# v1.net
KiCad netlist of a schematic drawn in EAGLE
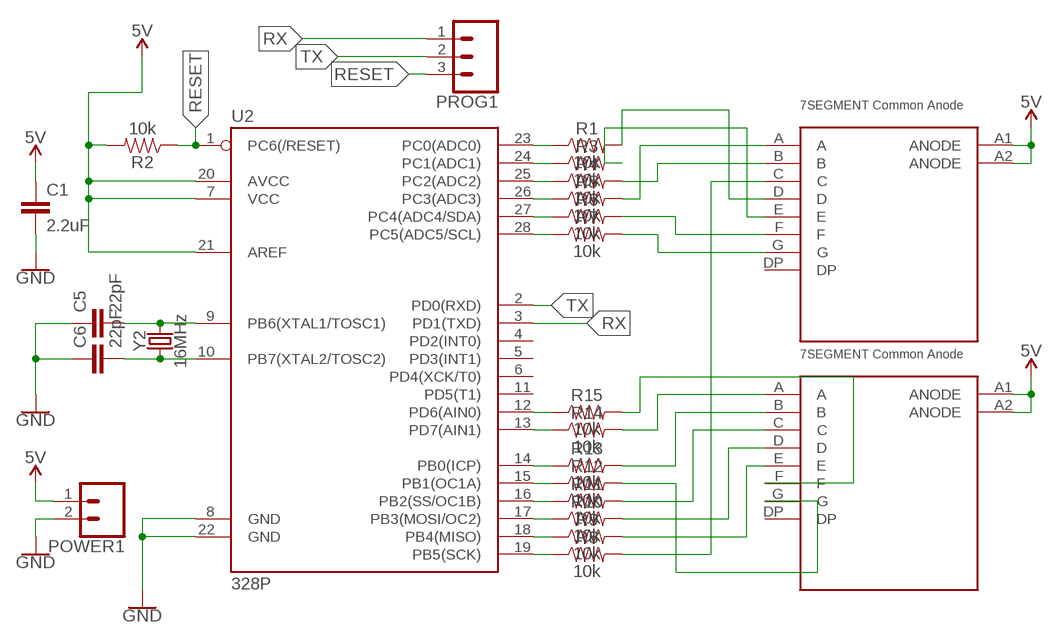
[diagram p0: schematic, sheet 1]

(export (version "E")
  (design (tool "Eeschema 10.0.6"))
  (components
    (comp (ref "C1")
      (value "2.2uF")
      (footprint "eagle-import:1206")
      (libsource (lib "eagle-import") (part "2.2UF-1206-50V-10%"))
    )
    (comp (ref "C5")
      (value "22pF")
      (footprint "eagle-import:CAP-PTH-2.54")
      (libsource (lib "eagle-import") (part "22PF-PTH-2.54MM-200V-5%"))
    )
    (comp (ref "C6")
      (value "22pF")
      (footprint "eagle-import:CAP-PTH-2.54")
      (libsource (lib "eagle-import") (part "22PF-PTH-2.54MM-200V-5%"))
    )
    (comp (ref "POWER1")
      (value "CONN_02")
      (footprint "eagle-import:1X02")
      (libsource (lib "eagle-import") (part "CONN_02"))
    )
    (comp (ref "PROG1")
      (value "CONN_03")
      (footprint "eagle-import:1X03")
      (libsource (lib "eagle-import") (part "CONN_03"))
    )
    (comp (ref "R1")
      (value "10k")
      (footprint "eagle-import:0805")
      (libsource (lib "eagle-import") (part "0.22OHM-0805-1/4W-1%"))
    )
    (comp (ref "R2")
      (value "10k")
      (footprint "eagle-import:AXIAL-0.3")
      (libsource (lib "eagle-import") (part "1KOHM-HORIZ-1/4W-1%"))
    )
    (comp (ref "R3")
      (value "10k")
      (footprint "eagle-import:0805")
      (libsource (lib "eagle-import") (part "0.22OHM-0805-1/4W-1%"))
    )
    (comp (ref "R4")
      (value "10k")
      (footprint "eagle-import:0805")
      (libsource (lib "eagle-import") (part "0.22OHM-0805-1/4W-1%"))
    )
    (comp (ref "R5")
      (value "10k")
      (footprint "eagle-import:0805")
      (libsource (lib "eagle-import") (part "0.22OHM-0805-1/4W-1%"))
    )
    (comp (ref "R6")
      (value "10k")
      (footprint "eagle-import:0805")
      (libsource (lib "eagle-import") (part "0.22OHM-0805-1/4W-1%"))
    )
    (comp (ref "R7")
      (value "10k")
      (footprint "eagle-import:0805")
      (libsource (lib "eagle-import") (part "0.22OHM-0805-1/4W-1%"))
    )
    (comp (ref "R8")
      (value "10k")
      (footprint "eagle-import:0805")
      (libsource (lib "eagle-import") (part "0.22OHM-0805-1/4W-1%"))
    )
    (comp (ref "R9")
      (value "10k")
      (footprint "eagle-import:0805")
      (libsource (lib "eagle-import") (part "0.22OHM-0805-1/4W-1%"))
    )
    (comp (ref "R10")
      (value "10k")
      (footprint "eagle-import:0805")
      (libsource (lib "eagle-import") (part "0.22OHM-0805-1/4W-1%"))
    )
    (comp (ref "R11")
      (value "10k")
      (footprint "eagle-import:0805")
      (libsource (lib "eagle-import") (part "0.22OHM-0805-1/4W-1%"))
    )
    (comp (ref "R12")
      (value "10k")
      (footprint "eagle-import:0805")
      (libsource (lib "eagle-import") (part "0.22OHM-0805-1/4W-1%"))
    )
    (comp (ref "R13")
      (value "10k")
      (footprint "eagle-import:0805")
      (libsource (lib "eagle-import") (part "0.22OHM-0805-1/4W-1%"))
    )
    (comp (ref "R14")
      (value "10k")
      (footprint "eagle-import:0805")
      (libsource (lib "eagle-import") (part "0.22OHM-0805-1/4W-1%"))
    )
    (comp (ref "R15")
      (value "10k")
      (footprint "eagle-import:0805")
      (libsource (lib "eagle-import") (part "0.22OHM-0805-1/4W-1%"))
    )
    (comp (ref "U$1")
      (value "7SEGMENTCA")
      (footprint "eagle-import:7SEGMENTCA")
      (libsource (lib "eagle-import") (part "7SEGMENTCA"))
    )
    (comp (ref "U$2")
      (value "7SEGMENTCA")
      (footprint "eagle-import:7SEGMENTCA")
      (libsource (lib "eagle-import") (part "7SEGMENTCA"))
    )
    (comp (ref "U2")
      (value "328P")
      (footprint "eagle-import:DIP28")
      (libsource (lib "eagle-import") (part "ATMEGA328P_PDIP"))
    )
    (comp (ref "Y2")
      (value "16MHz")
      (footprint "eagle-import:HC49US")
      (libsource (lib "eagle-import") (part "CRYSTAL-16MHZPTH-HC49US"))
    )
  )
  (nets
    (net (code "1") (name "5V") (class "Default")
      (node (ref "C1") (pin "1") (pinfunction "1_1") (pintype "passive"))
      (node (ref "POWER1") (pin "1") (pinfunction "1_1") (pintype "passive"))
      (node (ref "R2") (pin "P$2") (pinfunction "2_P$2") (pintype "passive"))
      (node (ref "U$1") (pin "A1") (pinfunction "ANODE_A1") (pintype "bidirectional"))
      (node (ref "U$1") (pin "A2") (pinfunction "ANODE_A2") (pintype "bidirectional"))
      (node (ref "U$2") (pin "A1") (pinfunction "ANODE_A1") (pintype "bidirectional"))
      (node (ref "U$2") (pin "A2") (pinfunction "ANODE_A2") (pintype "bidirectional"))
      (node (ref "U2") (pin "20") (pinfunction "AVCC_20") (pintype "bidirectional"))
      (node (ref "U2") (pin "21") (pinfunction "AREF_21") (pintype "bidirectional"))
      (node (ref "U2") (pin "7") (pinfunction "VCC_7") (pintype "bidirectional"))
    )
    (net (code "2") (name "GND") (class "Default")
      (node (ref "C1") (pin "2") (pinfunction "2_2") (pintype "passive"))
      (node (ref "C5") (pin "1") (pinfunction "1_1") (pintype "passive"))
      (node (ref "C6") (pin "1") (pinfunction "1_1") (pintype "passive"))
      (node (ref "POWER1") (pin "2") (pinfunction "2_2") (pintype "passive"))
      (node (ref "U2") (pin "22") (pinfunction "GND_22") (pintype "bidirectional"))
      (node (ref "U2") (pin "8") (pinfunction "GND_8") (pintype "bidirectional"))
    )
    (net (code "3") (name "Net-(R1-Pad2)") (class "Default")
      (node (ref "R1") (pin "2") (pinfunction "2_2") (pintype "passive"))
      (node (ref "U$1") (pin "D") (pinfunction "D_D") (pintype "bidirectional"))
    )
    (net (code "4") (name "Net-(R3-Pad2)") (class "Default")
      (node (ref "R3") (pin "2") (pinfunction "2_2") (pintype "passive"))
      (node (ref "U$1") (pin "E") (pinfunction "E_E") (pintype "bidirectional"))
    )
    (net (code "5") (name "Net-(R4-Pad2)") (class "Default")
      (node (ref "R4") (pin "2") (pinfunction "2_2") (pintype "passive"))
      (node (ref "U$1") (pin "B") (pinfunction "B_B") (pintype "bidirectional"))
    )
    (net (code "6") (name "Net-(R5-Pad2)") (class "Default")
      (node (ref "R5") (pin "2") (pinfunction "2_2") (pintype "passive"))
      (node (ref "U$1") (pin "A") (pinfunction "A_A") (pintype "bidirectional"))
    )
    (net (code "7") (name "Net-(R6-Pad2)") (class "Default")
      (node (ref "R6") (pin "2") (pinfunction "2_2") (pintype "passive"))
      (node (ref "U$1") (pin "F") (pinfunction "F_F") (pintype "bidirectional"))
    )
    (net (code "8") (name "Net-(R7-Pad2)") (class "Default")
      (node (ref "R7") (pin "2") (pinfunction "2_2") (pintype "passive"))
      (node (ref "U$1") (pin "G") (pinfunction "G_G") (pintype "bidirectional"))
    )
    (net (code "9") (name "Net-(R8-Pad2)") (class "Default")
      (node (ref "R8") (pin "2") (pinfunction "2_2") (pintype "passive"))
      (node (ref "U$1") (pin "C") (pinfunction "C_C") (pintype "bidirectional"))
    )
    (net (code "10") (name "Net-(R9-Pad2)") (class "Default")
      (node (ref "R9") (pin "2") (pinfunction "2_2") (pintype "passive"))
      (node (ref "U$2") (pin "E") (pinfunction "E_E") (pintype "bidirectional"))
    )
    (net (code "11") (name "Net-(R10-Pad2)") (class "Default")
      (node (ref "R10") (pin "2") (pinfunction "2_2") (pintype "passive"))
      (node (ref "U$2") (pin "D") (pinfunction "D_D") (pintype "bidirectional"))
    )
    (net (code "12") (name "Net-(R11-Pad2)") (class "Default")
      (node (ref "R11") (pin "2") (pinfunction "2_2") (pintype "passive"))
      (node (ref "U$2") (pin "C") (pinfunction "C_C") (pintype "bidirectional"))
    )
    (net (code "13") (name "Net-(R12-Pad2)") (class "Default")
      (node (ref "R12") (pin "2") (pinfunction "2_2") (pintype "passive"))
      (node (ref "U$2") (pin "G") (pinfunction "G_G") (pintype "bidirectional"))
    )
    (net (code "14") (name "Net-(R13-Pad2)") (class "Default")
      (node (ref "R13") (pin "2") (pinfunction "2_2") (pintype "passive"))
      (node (ref "U$2") (pin "B") (pinfunction "B_B") (pintype "bidirectional"))
    )
    (net (code "15") (name "Net-(R14-Pad2)") (class "Default")
      (node (ref "R14") (pin "2") (pinfunction "2_2") (pintype "passive"))
      (node (ref "U$2") (pin "A") (pinfunction "A_A") (pintype "bidirectional"))
    )
    (net (code "16") (name "Net-(R15-Pad2)") (class "Default")
      (node (ref "R15") (pin "2") (pinfunction "2_2") (pintype "passive"))
      (node (ref "U$2") (pin "F") (pinfunction "F_F") (pintype "bidirectional"))
    )
    (net (code "17") (name "Net-(U2-PB0(ICP))") (class "Default")
      (node (ref "R13") (pin "1") (pinfunction "1_1") (pintype "passive"))
      (node (ref "U2") (pin "14") (pinfunction "PB0(ICP)_14") (pintype "bidirectional"))
    )
    (net (code "18") (name "Net-(U2-PB1(OC1A))") (class "Default")
      (node (ref "R12") (pin "1") (pinfunction "1_1") (pintype "passive"))
      (node (ref "U2") (pin "15") (pinfunction "PB1(OC1A)_15") (pintype "bidirectional"))
    )
    (net (code "19") (name "Net-(U2-PB2(SS{slash}OC1B))") (class "Default")
      (node (ref "R11") (pin "1") (pinfunction "1_1") (pintype "passive"))
      (node (ref "U2") (pin "16") (pinfunction "PB2(SS/OC1B)_16") (pintype "bidirectional"))
    )
    (net (code "20") (name "Net-(U2-PB3(MOSI{slash}OC2))") (class "Default")
      (node (ref "R10") (pin "1") (pinfunction "1_1") (pintype "passive"))
      (node (ref "U2") (pin "17") (pinfunction "PB3(MOSI/OC2)_17") (pintype "bidirectional"))
    )
    (net (code "21") (name "Net-(U2-PB4(MISO))") (class "Default")
      (node (ref "R9") (pin "1") (pinfunction "1_1") (pintype "passive"))
      (node (ref "U2") (pin "18") (pinfunction "PB4(MISO)_18") (pintype "bidirectional"))
    )
    (net (code "22") (name "Net-(U2-PB5(SCK))") (class "Default")
      (node (ref "R8") (pin "1") (pinfunction "1_1") (pintype "passive"))
      (node (ref "U2") (pin "19") (pinfunction "PB5(SCK)_19") (pintype "bidirectional"))
    )
    (net (code "23") (name "Net-(U2-PB6(XTAL1{slash}TOSC1))") (class "Default")
      (node (ref "C5") (pin "2") (pinfunction "2_2") (pintype "passive"))
      (node (ref "U2") (pin "9") (pinfunction "PB6(XTAL1/TOSC1)_9") (pintype "bidirectional"))
      (node (ref "Y2") (pin "2") (pinfunction "2_2") (pintype "passive"))
    )
    (net (code "24") (name "Net-(U2-PB7(XTAL2{slash}TOSC2))") (class "Default")
      (node (ref "C6") (pin "2") (pinfunction "2_2") (pintype "passive"))
      (node (ref "U2") (pin "10") (pinfunction "PB7(XTAL2/TOSC2)_10") (pintype "bidirectional"))
      (node (ref "Y2") (pin "1") (pinfunction "1_1") (pintype "passive"))
    )
    (net (code "25") (name "Net-(U2-PC0(ADC0))") (class "Default")
      (node (ref "R1") (pin "1") (pinfunction "1_1") (pintype "passive"))
      (node (ref "U2") (pin "23") (pinfunction "PC0(ADC0)_23") (pintype "bidirectional"))
    )
    (net (code "26") (name "Net-(U2-PC1(ADC1))") (class "Default")
      (node (ref "R3") (pin "1") (pinfunction "1_1") (pintype "passive"))
      (node (ref "U2") (pin "24") (pinfunction "PC1(ADC1)_24") (pintype "bidirectional"))
    )
    (net (code "27") (name "Net-(U2-PC2(ADC2))") (class "Default")
      (node (ref "R4") (pin "1") (pinfunction "1_1") (pintype "passive"))
      (node (ref "U2") (pin "25") (pinfunction "PC2(ADC2)_25") (pintype "bidirectional"))
    )
    (net (code "28") (name "Net-(U2-PC3(ADC3))") (class "Default")
      (node (ref "R5") (pin "1") (pinfunction "1_1") (pintype "passive"))
      (node (ref "U2") (pin "26") (pinfunction "PC3(ADC3)_26") (pintype "bidirectional"))
    )
    (net (code "29") (name "Net-(U2-PC4(ADC4{slash}SDA))") (class "Default")
      (node (ref "R6") (pin "1") (pinfunction "1_1") (pintype "passive"))
      (node (ref "U2") (pin "27") (pinfunction "PC4(ADC4/SDA)_27") (pintype "bidirectional"))
    )
    (net (code "30") (name "Net-(U2-PC5(ADC5{slash}SCL))") (class "Default")
      (node (ref "R7") (pin "1") (pinfunction "1_1") (pintype "passive"))
      (node (ref "U2") (pin "28") (pinfunction "PC5(ADC5/SCL)_28") (pintype "bidirectional"))
    )
    (net (code "31") (name "Net-(U2-PD6(AIN0))") (class "Default")
      (node (ref "R15") (pin "1") (pinfunction "1_1") (pintype "passive"))
      (node (ref "U2") (pin "12") (pinfunction "PD6(AIN0)_12") (pintype "bidirectional"))
    )
    (net (code "32") (name "Net-(U2-PD7(AIN1))") (class "Default")
      (node (ref "R14") (pin "1") (pinfunction "1_1") (pintype "passive"))
      (node (ref "U2") (pin "13") (pinfunction "PD7(AIN1)_13") (pintype "bidirectional"))
    )
    (net (code "33") (name "RESET") (class "Default")
      (node (ref "PROG1") (pin "3") (pinfunction "3_3") (pintype "passive"))
      (node (ref "R2") (pin "P$1") (pinfunction "1_P$1") (pintype "passive"))
      (node (ref "U2") (pin "1") (pinfunction "PC6(/RESET)_1") (pintype "bidirectional"))
    )
    (net (code "34") (name "RX") (class "Default")
      (node (ref "PROG1") (pin "1") (pinfunction "1_1") (pintype "passive"))
      (node (ref "U2") (pin "3") (pinfunction "PD1(TXD)_3") (pintype "bidirectional"))
    )
    (net (code "35") (name "TX") (class "Default")
      (node (ref "PROG1") (pin "2") (pinfunction "2_2") (pintype "passive"))
      (node (ref "U2") (pin "2") (pinfunction "PD0(RXD)_2") (pintype "bidirectional"))
    )
    (net (code "36") (name "unconnected-(U$1-PadDP)") (class "Default")
      (node (ref "U$1") (pin "DP") (pinfunction "DP_DP") (pintype "bidirectional"))
    )
    (net (code "37") (name "unconnected-(U$2-PadDP)") (class "Default")
      (node (ref "U$2") (pin "DP") (pinfunction "DP_DP") (pintype "bidirectional"))
    )
    (net (code "38") (name "unconnected-(U2-PD2(INT0)-Pad4)") (class "Default")
      (node (ref "U2") (pin "4") (pinfunction "PD2(INT0)_4") (pintype "bidirectional"))
    )
    (net (code "39") (name "unconnected-(U2-PD3(INT1)-Pad5)") (class "Default")
      (node (ref "U2") (pin "5") (pinfunction "PD3(INT1)_5") (pintype "bidirectional"))
    )
    (net (code "40") (name "unconnected-(U2-PD4(XCK{slash}T0)-Pad6)") (class "Default")
      (node (ref "U2") (pin "6") (pinfunction "PD4(XCK/T0)_6") (pintype "bidirectional"))
    )
    (net (code "41") (name "unconnected-(U2-PD5(T1)-Pad11)") (class "Default")
      (node (ref "U2") (pin "11") (pinfunction "PD5(T1)_11") (pintype "bidirectional"))
    )
  )
)
